# Injectors.net
KiCad netlist of a schematic drawn in Altium Designer
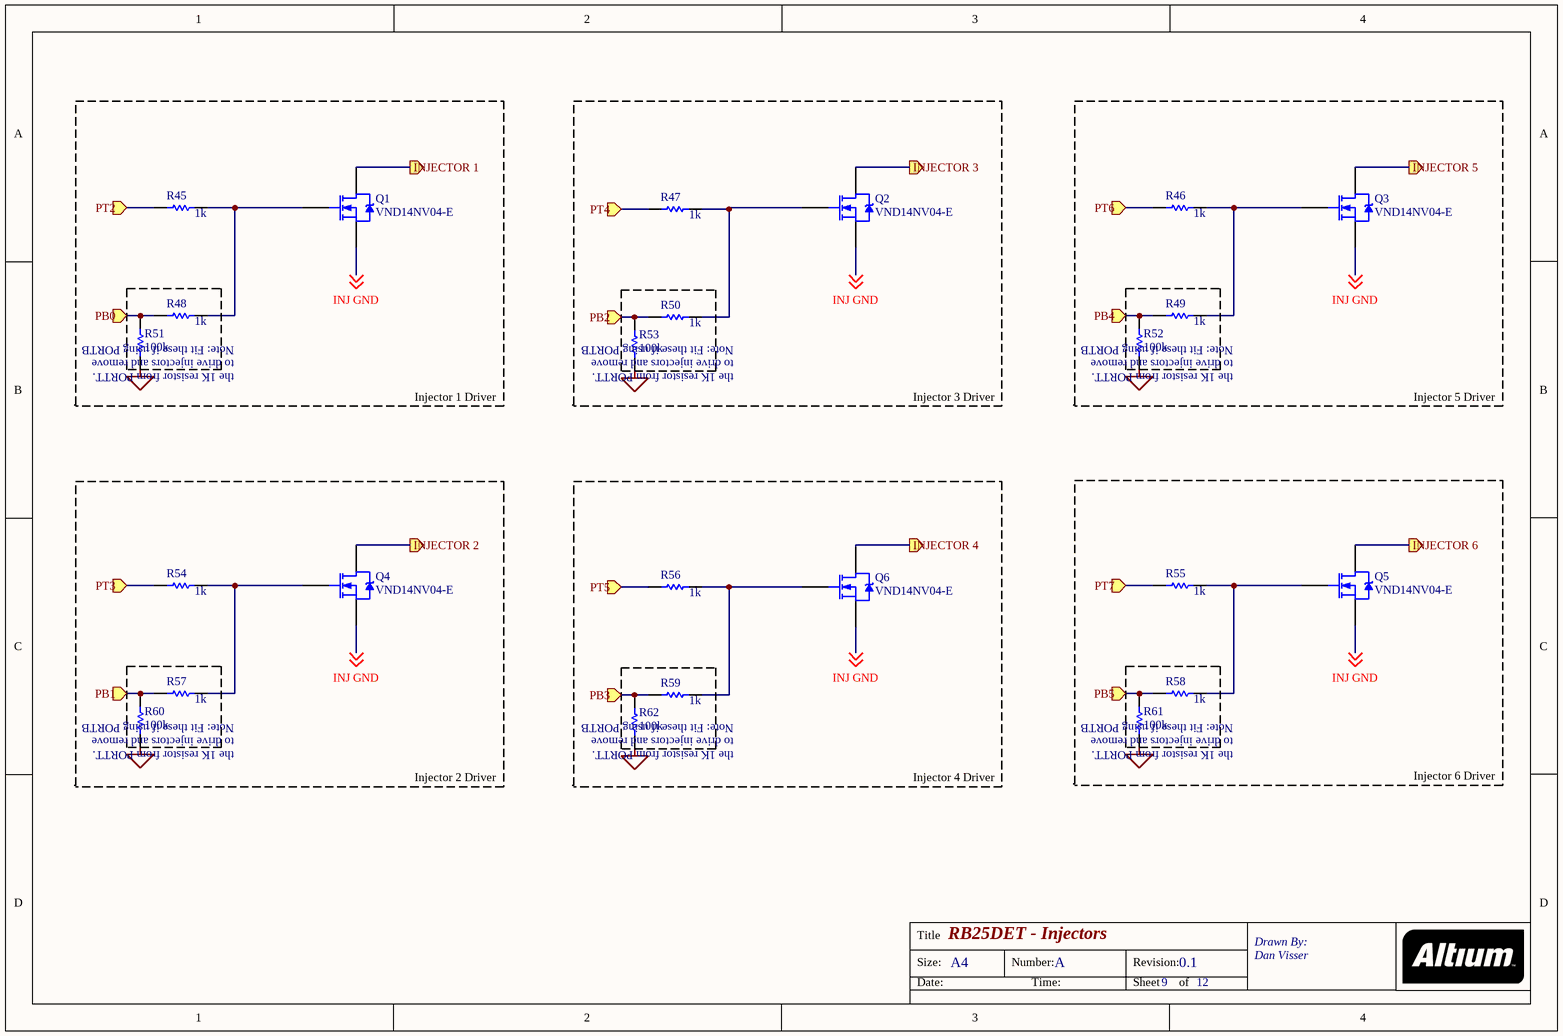
[diagram p0: Injectors.SchDoc]

(export (version "E")
  (design (tool "Eeschema 10.0.6"))
  (components
    (comp (ref "Q1")
      (value "VND14NV04-E")
      (footprint "TO-220AB")
      (description "HEXFET Power MOSFET")
      (fields (field (name "PUBLISHER") "Altium Limited"))
      (libsource (lib "IR Discrete MOSFET - Power") (part "IRL520N"))
    )
    (comp (ref "Q2")
      (value "VND14NV04-E")
      (footprint "TO-220AB")
      (description "HEXFET Power MOSFET")
      (fields (field (name "PUBLISHER") "Altium Limited"))
      (libsource (lib "IR Discrete MOSFET - Power") (part "IRL520N"))
    )
    (comp (ref "Q3")
      (value "VND14NV04-E")
      (footprint "TO-220AB")
      (description "HEXFET Power MOSFET")
      (fields (field (name "PUBLISHER") "Altium Limited"))
      (libsource (lib "IR Discrete MOSFET - Power") (part "IRL520N"))
    )
    (comp (ref "Q4")
      (value "VND14NV04-E")
      (footprint "TO-220AB")
      (description "HEXFET Power MOSFET")
      (fields (field (name "PUBLISHER") "Altium Limited"))
      (libsource (lib "IR Discrete MOSFET - Power") (part "IRL520N"))
    )
    (comp (ref "Q5")
      (value "VND14NV04-E")
      (footprint "TO-220AB")
      (description "HEXFET Power MOSFET")
      (fields (field (name "PUBLISHER") "Altium Limited"))
      (libsource (lib "IR Discrete MOSFET - Power") (part "IRL520N"))
    )
    (comp (ref "Q6")
      (value "VND14NV04-E")
      (footprint "TO-220AB")
      (description "HEXFET Power MOSFET")
      (fields (field (name "PUBLISHER") "Altium Limited"))
      (libsource (lib "IR Discrete MOSFET - Power") (part "IRL520N"))
    )
    (comp (ref "R45")
      (value "1k")
      (footprint "AXIAL-0.3")
      (description "Resistor")
      (fields (field (name "PUBLISHER") "Altium Limited"))
      (libsource (lib "Miscellaneous Devices") (part "Res1"))
    )
    (comp (ref "R46")
      (value "1k")
      (footprint "AXIAL-0.3")
      (description "Resistor")
      (fields (field (name "PUBLISHER") "Altium Limited"))
      (libsource (lib "Miscellaneous Devices") (part "Res1"))
    )
    (comp (ref "R47")
      (value "1k")
      (footprint "AXIAL-0.3")
      (description "Resistor")
      (fields (field (name "PUBLISHER") "Altium Limited"))
      (libsource (lib "Miscellaneous Devices") (part "Res1"))
    )
    (comp (ref "R48")
      (value "1k")
      (footprint "AXIAL-0.3")
      (description "Resistor")
      (fields (field (name "PUBLISHER") "Altium Limited"))
      (libsource (lib "Miscellaneous Devices") (part "Res1"))
    )
    (comp (ref "R49")
      (value "1k")
      (footprint "AXIAL-0.3")
      (description "Resistor")
      (fields (field (name "PUBLISHER") "Altium Limited"))
      (libsource (lib "Miscellaneous Devices") (part "Res1"))
    )
    (comp (ref "R50")
      (value "1k")
      (footprint "AXIAL-0.3")
      (description "Resistor")
      (fields (field (name "PUBLISHER") "Altium Limited"))
      (libsource (lib "Miscellaneous Devices") (part "Res1"))
    )
    (comp (ref "R51")
      (value "100k")
      (footprint "AXIAL-0.3")
      (description "Resistor")
      (fields (field (name "PUBLISHER") "Altium Limited"))
      (libsource (lib "Miscellaneous Devices") (part "Res1"))
    )
    (comp (ref "R52")
      (value "100k")
      (footprint "AXIAL-0.3")
      (description "Resistor")
      (fields (field (name "PUBLISHER") "Altium Limited"))
      (libsource (lib "Miscellaneous Devices") (part "Res1"))
    )
    (comp (ref "R53")
      (value "100k")
      (footprint "AXIAL-0.3")
      (description "Resistor")
      (fields (field (name "PUBLISHER") "Altium Limited"))
      (libsource (lib "Miscellaneous Devices") (part "Res1"))
    )
    (comp (ref "R54")
      (value "1k")
      (footprint "AXIAL-0.3")
      (description "Resistor")
      (fields (field (name "PUBLISHER") "Altium Limited"))
      (libsource (lib "Miscellaneous Devices") (part "Res1"))
    )
    (comp (ref "R55")
      (value "1k")
      (footprint "AXIAL-0.3")
      (description "Resistor")
      (fields (field (name "PUBLISHER") "Altium Limited"))
      (libsource (lib "Miscellaneous Devices") (part "Res1"))
    )
    (comp (ref "R56")
      (value "1k")
      (footprint "AXIAL-0.3")
      (description "Resistor")
      (fields (field (name "PUBLISHER") "Altium Limited"))
      (libsource (lib "Miscellaneous Devices") (part "Res1"))
    )
    (comp (ref "R57")
      (value "1k")
      (footprint "AXIAL-0.3")
      (description "Resistor")
      (fields (field (name "PUBLISHER") "Altium Limited"))
      (libsource (lib "Miscellaneous Devices") (part "Res1"))
    )
    (comp (ref "R58")
      (value "1k")
      (footprint "AXIAL-0.3")
      (description "Resistor")
      (fields (field (name "PUBLISHER") "Altium Limited"))
      (libsource (lib "Miscellaneous Devices") (part "Res1"))
    )
    (comp (ref "R59")
      (value "1k")
      (footprint "AXIAL-0.3")
      (description "Resistor")
      (fields (field (name "PUBLISHER") "Altium Limited"))
      (libsource (lib "Miscellaneous Devices") (part "Res1"))
    )
    (comp (ref "R60")
      (value "100k")
      (footprint "AXIAL-0.3")
      (description "Resistor")
      (fields (field (name "PUBLISHER") "Altium Limited"))
      (libsource (lib "Miscellaneous Devices") (part "Res1"))
    )
    (comp (ref "R61")
      (value "100k")
      (footprint "AXIAL-0.3")
      (description "Resistor")
      (fields (field (name "PUBLISHER") "Altium Limited"))
      (libsource (lib "Miscellaneous Devices") (part "Res1"))
    )
    (comp (ref "R62")
      (value "100k")
      (footprint "AXIAL-0.3")
      (description "Resistor")
      (fields (field (name "PUBLISHER") "Altium Limited"))
      (libsource (lib "Miscellaneous Devices") (part "Res1"))
    )
  )
  (nets
    (net (code "1") (name "/INJECTOR 1") (class "Default")
      (node (ref "Q1") (pin "2") (pinfunction "D_2") (pintype "passive"))
    )
    (net (code "2") (name "/INJECTOR 2") (class "Default")
      (node (ref "Q4") (pin "2") (pinfunction "D_2") (pintype "passive"))
    )
    (net (code "3") (name "/INJECTOR 3") (class "Default")
      (node (ref "Q2") (pin "2") (pinfunction "D_2") (pintype "passive"))
    )
    (net (code "4") (name "/INJECTOR 4") (class "Default")
      (node (ref "Q6") (pin "2") (pinfunction "D_2") (pintype "passive"))
    )
    (net (code "5") (name "/INJECTOR 5") (class "Default")
      (node (ref "Q3") (pin "2") (pinfunction "D_2") (pintype "passive"))
    )
    (net (code "6") (name "/INJECTOR 6") (class "Default")
      (node (ref "Q5") (pin "2") (pinfunction "D_2") (pintype "passive"))
    )
    (net (code "7") (name "/PB0") (class "Default")
      (node (ref "R48") (pin "1") (pinfunction "1_1") (pintype "passive"))
      (node (ref "R51") (pin "2") (pinfunction "2_2") (pintype "passive"))
    )
    (net (code "8") (name "/PB1") (class "Default")
      (node (ref "R57") (pin "1") (pinfunction "1_1") (pintype "passive"))
      (node (ref "R60") (pin "2") (pinfunction "2_2") (pintype "passive"))
    )
    (net (code "9") (name "/PB2") (class "Default")
      (node (ref "R50") (pin "1") (pinfunction "1_1") (pintype "passive"))
      (node (ref "R53") (pin "2") (pinfunction "2_2") (pintype "passive"))
    )
    (net (code "10") (name "/PB3") (class "Default")
      (node (ref "R59") (pin "1") (pinfunction "1_1") (pintype "passive"))
      (node (ref "R62") (pin "2") (pinfunction "2_2") (pintype "passive"))
    )
    (net (code "11") (name "/PB4") (class "Default")
      (node (ref "R49") (pin "1") (pinfunction "1_1") (pintype "passive"))
      (node (ref "R52") (pin "2") (pinfunction "2_2") (pintype "passive"))
    )
    (net (code "12") (name "/PB5") (class "Default")
      (node (ref "R58") (pin "1") (pinfunction "1_1") (pintype "passive"))
      (node (ref "R61") (pin "2") (pinfunction "2_2") (pintype "passive"))
    )
    (net (code "13") (name "/PT2") (class "Default")
      (node (ref "R45") (pin "1") (pinfunction "1_1") (pintype "passive"))
    )
    (net (code "14") (name "/PT3") (class "Default")
      (node (ref "R54") (pin "1") (pinfunction "1_1") (pintype "passive"))
    )
    (net (code "15") (name "/PT4") (class "Default")
      (node (ref "R47") (pin "1") (pinfunction "1_1") (pintype "passive"))
    )
    (net (code "16") (name "/PT5") (class "Default")
      (node (ref "R56") (pin "1") (pinfunction "1_1") (pintype "passive"))
    )
    (net (code "17") (name "/PT6") (class "Default")
      (node (ref "R46") (pin "1") (pinfunction "1_1") (pintype "passive"))
    )
    (net (code "18") (name "/PT7") (class "Default")
      (node (ref "R55") (pin "1") (pinfunction "1_1") (pintype "passive"))
    )
    (net (code "19") (name "<NO NET>") (class "Default")
      (node (ref "R51") (pin "1") (pinfunction "1_1") (pintype "passive"))
      (node (ref "R52") (pin "1") (pinfunction "1_1") (pintype "passive"))
      (node (ref "R53") (pin "1") (pinfunction "1_1") (pintype "passive"))
      (node (ref "R60") (pin "1") (pinfunction "1_1") (pintype "passive"))
      (node (ref "R61") (pin "1") (pinfunction "1_1") (pintype "passive"))
      (node (ref "R62") (pin "1") (pinfunction "1_1") (pintype "passive"))
    )
    (net (code "20") (name "INJ GND") (class "Default")
      (node (ref "Q1") (pin "3") (pinfunction "S_3") (pintype "passive"))
      (node (ref "Q2") (pin "3") (pinfunction "S_3") (pintype "passive"))
      (node (ref "Q3") (pin "3") (pinfunction "S_3") (pintype "passive"))
      (node (ref "Q4") (pin "3") (pinfunction "S_3") (pintype "passive"))
      (node (ref "Q5") (pin "3") (pinfunction "S_3") (pintype "passive"))
      (node (ref "Q6") (pin "3") (pinfunction "S_3") (pintype "passive"))
    )
    (net (code "21") (name "Net-(Q1-G)") (class "Default")
      (node (ref "Q1") (pin "1") (pinfunction "G_1") (pintype "passive"))
      (node (ref "R45") (pin "2") (pinfunction "2_2") (pintype "passive"))
      (node (ref "R48") (pin "2") (pinfunction "2_2") (pintype "passive"))
    )
    (net (code "22") (name "Net-(Q2-G)") (class "Default")
      (node (ref "Q2") (pin "1") (pinfunction "G_1") (pintype "passive"))
      (node (ref "R47") (pin "2") (pinfunction "2_2") (pintype "passive"))
      (node (ref "R50") (pin "2") (pinfunction "2_2") (pintype "passive"))
    )
    (net (code "23") (name "Net-(Q3-G)") (class "Default")
      (node (ref "Q3") (pin "1") (pinfunction "G_1") (pintype "passive"))
      (node (ref "R46") (pin "2") (pinfunction "2_2") (pintype "passive"))
      (node (ref "R49") (pin "2") (pinfunction "2_2") (pintype "passive"))
    )
    (net (code "24") (name "Net-(Q4-G)") (class "Default")
      (node (ref "Q4") (pin "1") (pinfunction "G_1") (pintype "passive"))
      (node (ref "R54") (pin "2") (pinfunction "2_2") (pintype "passive"))
      (node (ref "R57") (pin "2") (pinfunction "2_2") (pintype "passive"))
    )
    (net (code "25") (name "Net-(Q5-G)") (class "Default")
      (node (ref "Q5") (pin "1") (pinfunction "G_1") (pintype "passive"))
      (node (ref "R55") (pin "2") (pinfunction "2_2") (pintype "passive"))
      (node (ref "R58") (pin "2") (pinfunction "2_2") (pintype "passive"))
    )
    (net (code "26") (name "Net-(Q6-G)") (class "Default")
      (node (ref "Q6") (pin "1") (pinfunction "G_1") (pintype "passive"))
      (node (ref "R56") (pin "2") (pinfunction "2_2") (pintype "passive"))
      (node (ref "R59") (pin "2") (pinfunction "2_2") (pintype "passive"))
    )
  )
)
